# ERpcuk.net
KiCad netlist of a schematic drawn in EAGLE
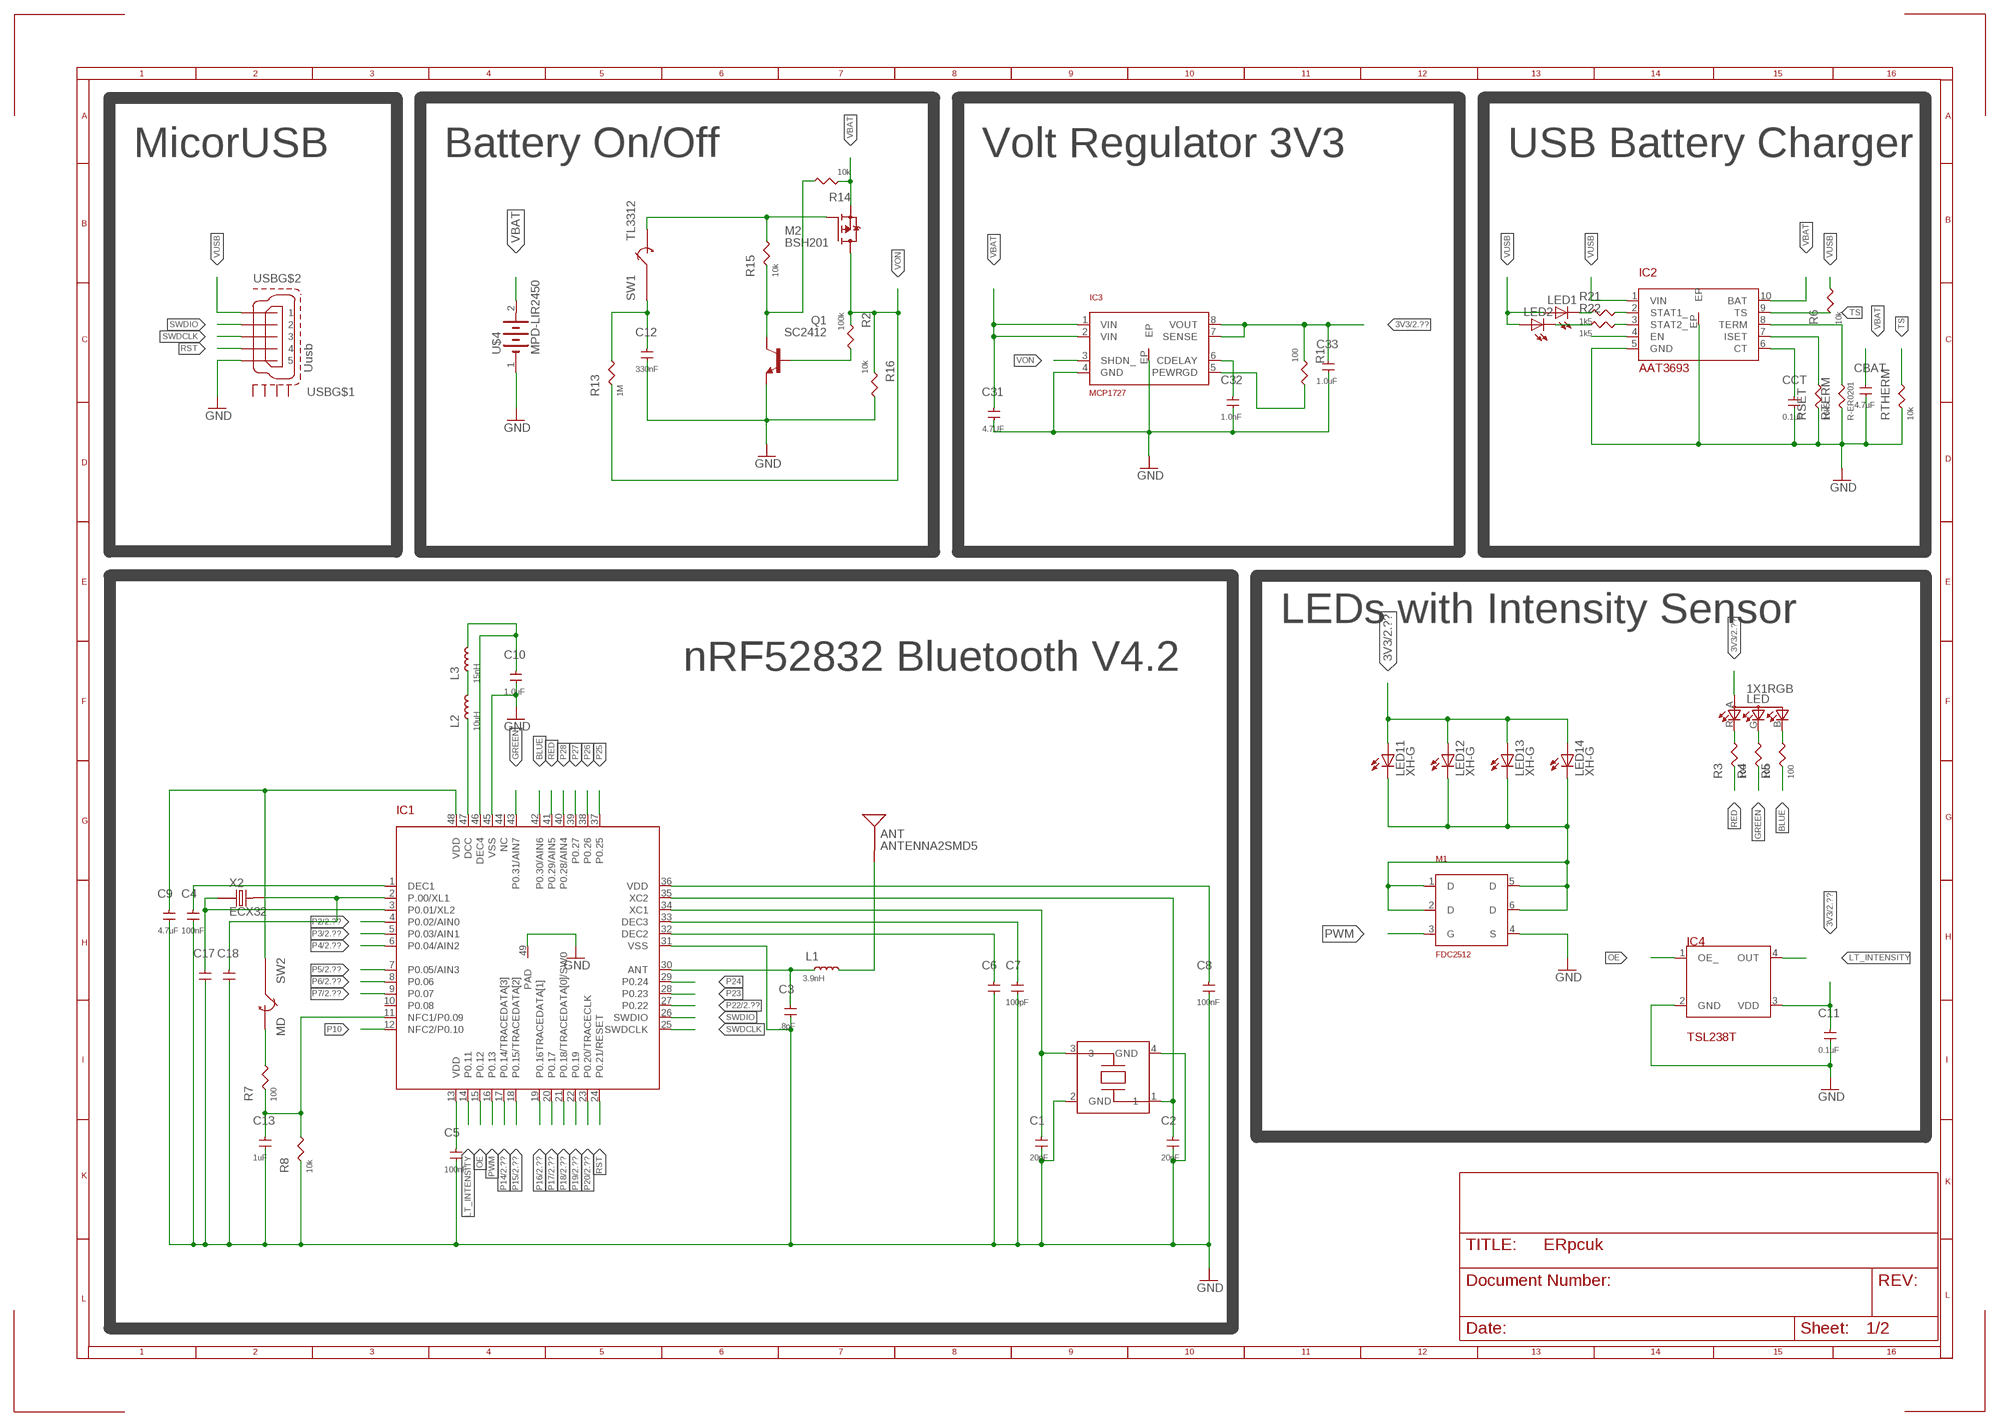
[diagram p0: schematic, sheet 1]
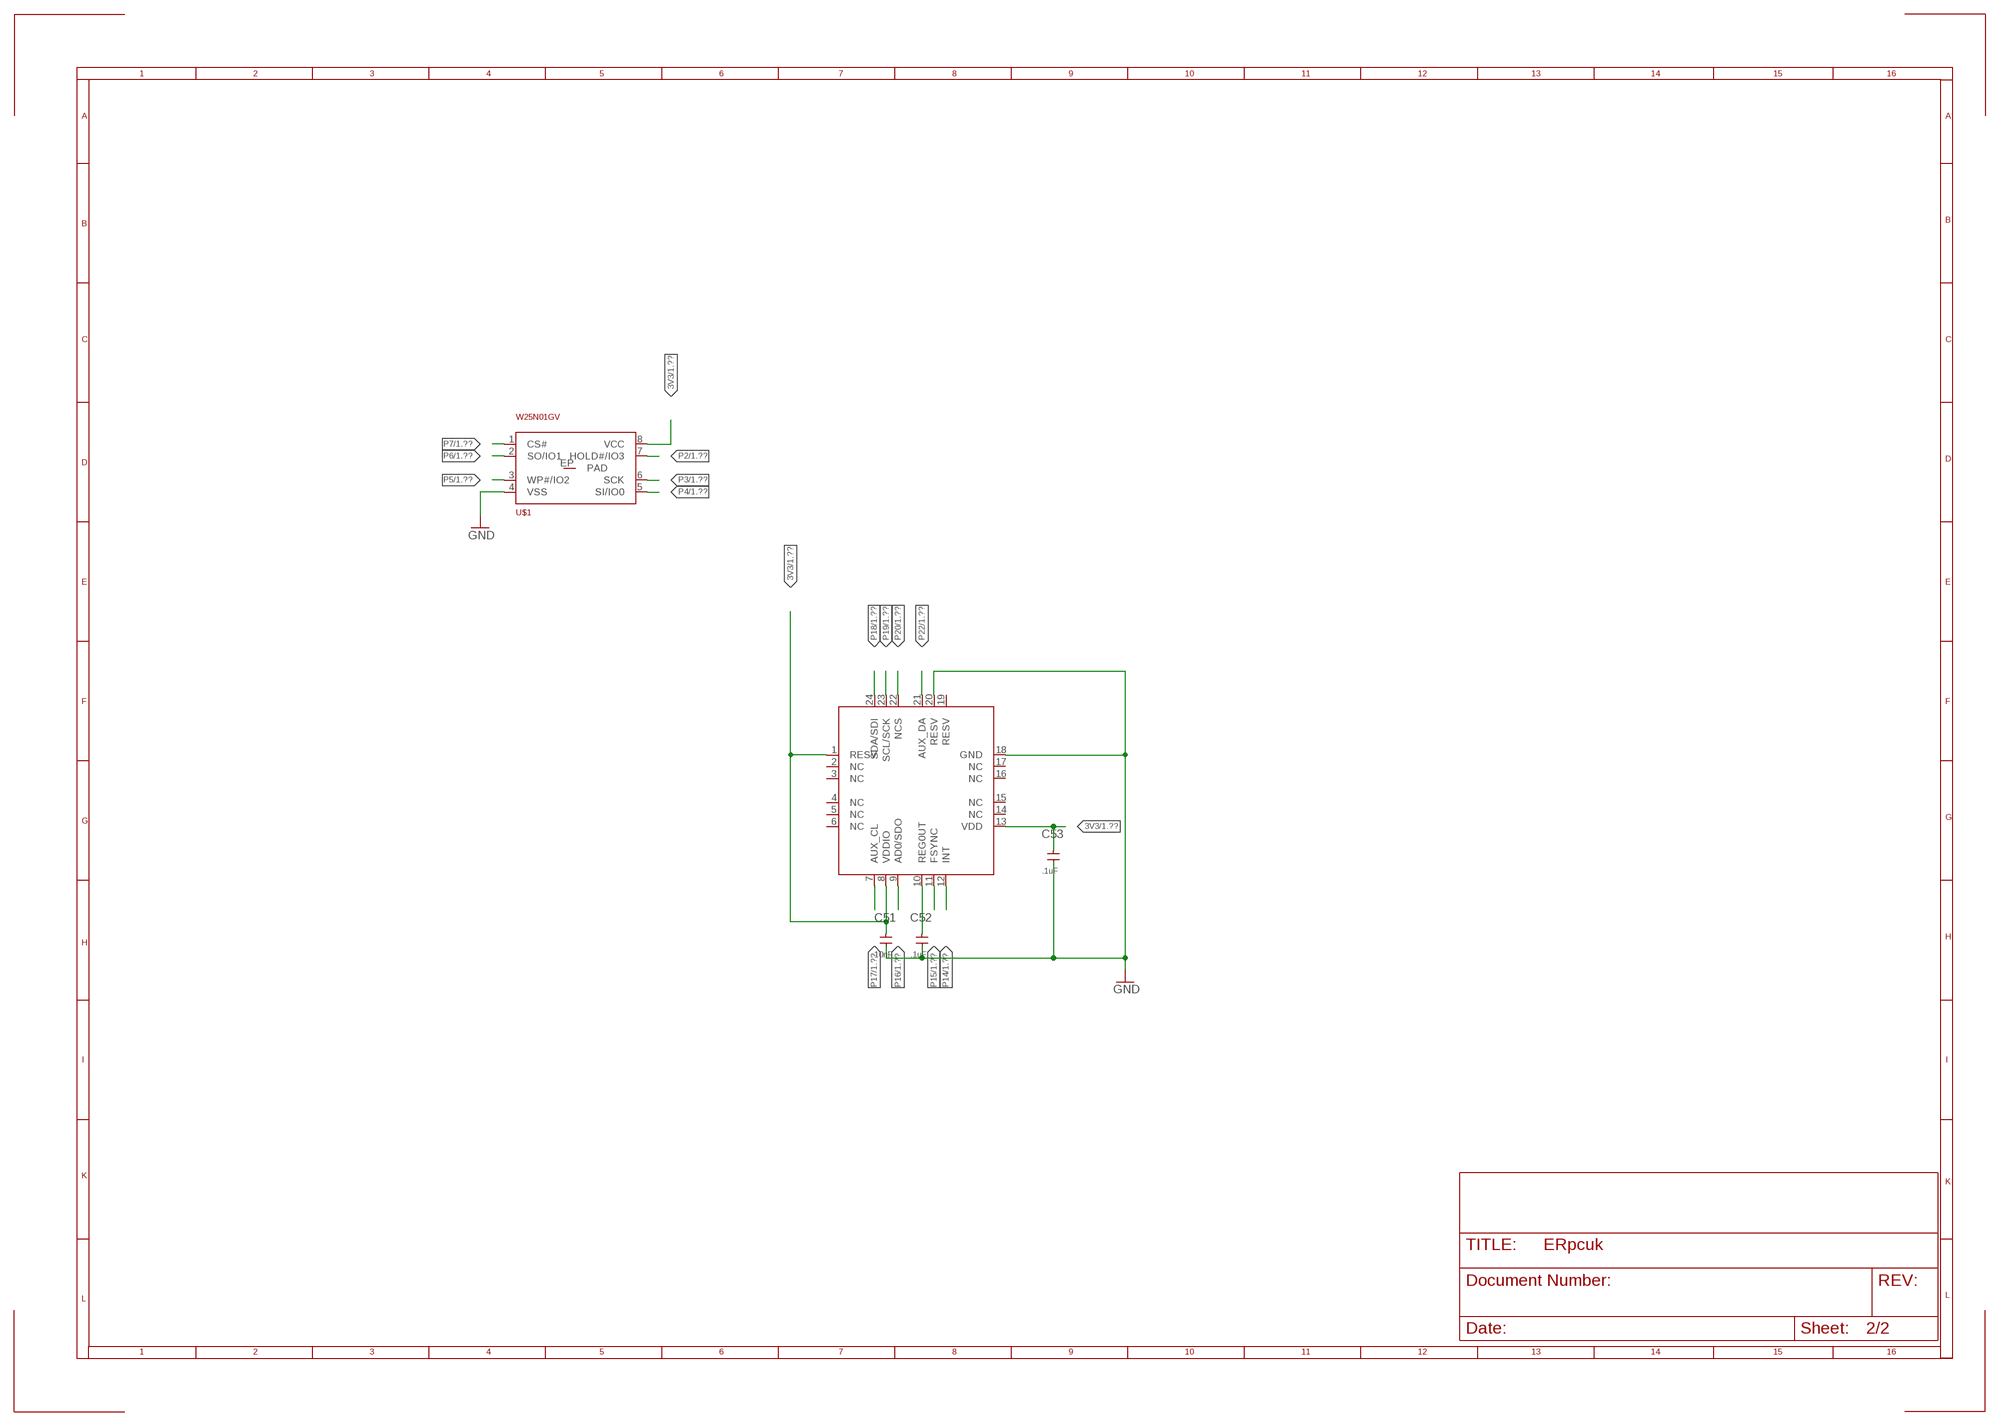
[diagram p1: schematic, sheet 2]

(export (version "E")
  (design (tool "Eeschema 10.0.6"))
  (components
    (comp (ref "C51")
      (value "10nF")
      (footprint "eagle-import:C0201")
      (libsource (lib "eagle-import") (part "C-ER201"))
    )
    (comp (ref "C52")
      (value ".1uF")
      (footprint "eagle-import:C0201")
      (libsource (lib "eagle-import") (part "C-ER201"))
    )
    (comp (ref "C53")
      (value ".1uF")
      (footprint "eagle-import:C0201")
      (libsource (lib "eagle-import") (part "C-ER201"))
    )
    (comp (ref "IC5")
      (value "MPU9250")
      (footprint "eagle-import:3X3_24_QFN_CORRECTED")
      (libsource (lib "eagle-import") (part "MPU9250_CORRECTED"))
    )
    (comp (ref "U$1")
      (value "W25N01GV")
      (footprint "eagle-import:8WSON6X8")
      (libsource (lib "eagle-import") (part "W25N01GV"))
    )
    (comp (ref "ANT")
      (value "ANTENNA2SMD5")
      (footprint "eagle-import:ANTENNA-CHIP5")
      (libsource (lib "eagle-import") (part "ANTENNA2SMD5"))
    )
    (comp (ref "C1")
      (value "20pF")
      (footprint "eagle-import:C0201")
      (libsource (lib "eagle-import") (part "C-ER201"))
    )
    (comp (ref "C2")
      (value "20pF")
      (footprint "eagle-import:C0201")
      (libsource (lib "eagle-import") (part "C-ER201"))
    )
    (comp (ref "C3")
      (value ".8pF")
      (footprint "eagle-import:C0201")
      (libsource (lib "eagle-import") (part "C-ER201"))
    )
    (comp (ref "C4")
      (value "100nF")
      (footprint "eagle-import:C0201")
      (libsource (lib "eagle-import") (part "C-ER201"))
    )
    (comp (ref "C5")
      (value "100nF")
      (footprint "eagle-import:C0201")
      (libsource (lib "eagle-import") (part "C-ER201"))
    )
    (comp (ref "C6")
      (value "C-ER201")
      (footprint "eagle-import:C0201")
      (libsource (lib "eagle-import") (part "C-ER201"))
    )
    (comp (ref "C7")
      (value "100pF")
      (footprint "eagle-import:C0201")
      (libsource (lib "eagle-import") (part "C-ER201"))
    )
    (comp (ref "C8")
      (value "100nF")
      (footprint "eagle-import:C0201")
      (libsource (lib "eagle-import") (part "C-ER201"))
    )
    (comp (ref "C9")
      (value "4.7uF")
      (footprint "eagle-import:C0402")
      (libsource (lib "eagle-import") (part "C-ERC0402"))
    )
    (comp (ref "C10")
      (value "1.0uF")
      (footprint "eagle-import:C0201")
      (libsource (lib "eagle-import") (part "C-ER201"))
    )
    (comp (ref "C11")
      (value "0.1uF")
      (footprint "eagle-import:C0201")
      (libsource (lib "eagle-import") (part "C-ER201"))
    )
    (comp (ref "C12")
      (value "330nF")
      (footprint "eagle-import:C0201")
      (libsource (lib "eagle-import") (part "C-ER201"))
    )
    (comp (ref "C13")
      (value "1uF")
      (footprint "eagle-import:C0201")
      (libsource (lib "eagle-import") (part "C-ER201"))
    )
    (comp (ref "C17")
      (value "C-ER201")
      (footprint "eagle-import:C0201")
      (libsource (lib "eagle-import") (part "C-ER201"))
    )
    (comp (ref "C18")
      (value "C-ER201")
      (footprint "eagle-import:C0201")
      (libsource (lib "eagle-import") (part "C-ER201"))
    )
    (comp (ref "C31")
      (value "4.7UF")
      (footprint "eagle-import:C0402")
      (libsource (lib "eagle-import") (part "C-ERC0402"))
    )
    (comp (ref "C32")
      (value "1.0nF")
      (footprint "eagle-import:C0201")
      (libsource (lib "eagle-import") (part "C-ER201"))
    )
    (comp (ref "C33")
      (value "1.0uF")
      (footprint "eagle-import:C0201")
      (libsource (lib "eagle-import") (part "C-ER201"))
    )
    (comp (ref "CBAT")
      (value "4.7uF")
      (footprint "eagle-import:C0402")
      (libsource (lib "eagle-import") (part "C-ERC0402"))
    )
    (comp (ref "CCT")
      (value "0.1uF")
      (footprint "eagle-import:C0201")
      (libsource (lib "eagle-import") (part "C-ER201"))
    )
    (comp (ref "IC1")
      (value "NRF52832")
      (footprint "eagle-import:QFN48")
      (libsource (lib "eagle-import") (part "NRF52832"))
    )
    (comp (ref "IC2")
      (value "AAT3693")
      (footprint "eagle-import:AAT3693")
      (libsource (lib "eagle-import") (part "AAT3693"))
    )
    (comp (ref "IC3")
      (value "MCP1727")
      (footprint "eagle-import:DFN8-3X3")
      (libsource (lib "eagle-import") (part "MCP1727"))
    )
    (comp (ref "IC4")
      (value "TSL238T")
      (footprint "eagle-import:T4")
      (libsource (lib "eagle-import") (part "TSL238T"))
    )
    (comp (ref "L1")
      (value "3.9nH")
      (footprint "eagle-import:C0201")
      (libsource (lib "eagle-import") (part "L-ER0201"))
    )
    (comp (ref "L2")
      (value "10uH")
      (footprint "eagle-import:R0603")
      (libsource (lib "eagle-import") (part "L-ERL603"))
    )
    (comp (ref "L3")
      (value "15nH")
      (footprint "eagle-import:C0201")
      (libsource (lib "eagle-import") (part "L-ER0201"))
    )
    (comp (ref "LED")
      (value "1X1RGB")
      (footprint "eagle-import:1X1")
      (libsource (lib "eagle-import") (part "1X1RGB"))
    )
    (comp (ref "LED1")
      (value "LEDCHIP-LED0603")
      (footprint "eagle-import:CHIP-LED0603")
      (libsource (lib "eagle-import") (part "LEDCHIP-LED0603"))
    )
    (comp (ref "LED2")
      (value "LEDCHIP-LED0603")
      (footprint "eagle-import:CHIP-LED0603")
      (libsource (lib "eagle-import") (part "LEDCHIP-LED0603"))
    )
    (comp (ref "LED11")
      (value "XH-G")
      (footprint "eagle-import:XH-G")
      (libsource (lib "eagle-import") (part "XH-G"))
    )
    (comp (ref "LED12")
      (value "XH-G")
      (footprint "eagle-import:XH-G")
      (libsource (lib "eagle-import") (part "XH-G"))
    )
    (comp (ref "LED13")
      (value "XH-G")
      (footprint "eagle-import:XH-G")
      (libsource (lib "eagle-import") (part "XH-G"))
    )
    (comp (ref "LED14")
      (value "XH-G")
      (footprint "eagle-import:XH-G")
      (libsource (lib "eagle-import") (part "XH-G"))
    )
    (comp (ref "M1")
      (value "FDC2512")
      (footprint "eagle-import:SSOT6")
      (libsource (lib "eagle-import") (part "FDC2512"))
    )
    (comp (ref "M2")
      (value "BSH201")
      (footprint "eagle-import:SOT23")
      (libsource (lib "eagle-import") (part "BSH201"))
    )
    (comp (ref "Q1")
      (value "SC2412")
      (footprint "eagle-import:SC59-BEC")
      (libsource (lib "eagle-import") (part "SC2412"))
    )
    (comp (ref "R1")
      (value "100")
      (footprint "eagle-import:R0201")
      (libsource (lib "eagle-import") (part "R-ER0201"))
    )
    (comp (ref "R2")
      (value "100k")
      (footprint "eagle-import:R0201")
      (libsource (lib "eagle-import") (part "R-ER0201"))
    )
    (comp (ref "R3")
      (value "100")
      (footprint "eagle-import:R0201")
      (libsource (lib "eagle-import") (part "R-ER0201"))
    )
    (comp (ref "R4")
      (value "100")
      (footprint "eagle-import:R0201")
      (libsource (lib "eagle-import") (part "R-ER0201"))
    )
    (comp (ref "R5")
      (value "100")
      (footprint "eagle-import:R0201")
      (libsource (lib "eagle-import") (part "R-ER0201"))
    )
    (comp (ref "R6")
      (value "10k")
      (footprint "eagle-import:R0201")
      (libsource (lib "eagle-import") (part "R-ER0201"))
    )
    (comp (ref "R7")
      (value "100")
      (footprint "eagle-import:R0201")
      (libsource (lib "eagle-import") (part "R-ER0201"))
    )
    (comp (ref "R8")
      (value "10k")
      (footprint "eagle-import:R0201")
      (libsource (lib "eagle-import") (part "R-ER0201"))
    )
    (comp (ref "R13")
      (value "1M")
      (footprint "eagle-import:R0201")
      (libsource (lib "eagle-import") (part "R-ER0201"))
    )
    (comp (ref "R14")
      (value "10k")
      (footprint "eagle-import:R0201")
      (libsource (lib "eagle-import") (part "R-ER0201"))
    )
    (comp (ref "R15")
      (value "10k")
      (footprint "eagle-import:R0201")
      (libsource (lib "eagle-import") (part "R-ER0201"))
    )
    (comp (ref "R16")
      (value "10k")
      (footprint "eagle-import:R0201")
      (libsource (lib "eagle-import") (part "R-ER0201"))
    )
    (comp (ref "R21")
      (value "1k5")
      (footprint "eagle-import:R0201")
      (libsource (lib "eagle-import") (part "R-ER0201"))
    )
    (comp (ref "R22")
      (value "1k5")
      (footprint "eagle-import:R0201")
      (libsource (lib "eagle-import") (part "R-ER0201"))
    )
    (comp (ref "RSET")
      (value "16k5")
      (footprint "eagle-import:R0201")
      (libsource (lib "eagle-import") (part "R-ER0201"))
    )
    (comp (ref "RTERM")
      (value "R-ER0201")
      (footprint "eagle-import:R0201")
      (libsource (lib "eagle-import") (part "R-ER0201"))
    )
    (comp (ref "RTHERM")
      (value "10k")
      (footprint "eagle-import:R0201")
      (libsource (lib "eagle-import") (part "R-ER0201"))
    )
    (comp (ref "SW1")
      (value "TL3312")
      (footprint "eagle-import:TL3312")
      (libsource (lib "eagle-import") (part "TL3312"))
    )
    (comp (ref "SW2") (value "MD") (footprint "eagle-import:MD") (libsource (lib "eagle-import") (part "MD")))
    (comp (ref "U$4")
      (value "MPD-LIR2450")
      (footprint "eagle-import:LIR2450")
      (libsource (lib "eagle-import") (part "MPD-LIR2450"))
    )
    (comp (ref "USB")
      (value "Uusb")
      (footprint "eagle-import:ZX62R-B-5P")
      (libsource (lib "eagle-import") (part "MICRO-USB-SHIELD-ZX62R-B-5P"))
    )
    (comp (ref "X1")
      (value "FA-128")
      (footprint "eagle-import:FA-128")
      (libsource (lib "eagle-import") (part "FA-128"))
    )
    (comp (ref "X2")
      (value "ECX32")
      (footprint "eagle-import:ECX39")
      (libsource (lib "eagle-import") (part "ECX32"))
    )
  )
  (nets
    (net (code "1") (name "3V3") (class "Default")
      (node (ref "C11") (pin "2") (pinfunction "P$2_2") (pintype "bidirectional"))
      (node (ref "C33") (pin "2") (pinfunction "P$2_2") (pintype "bidirectional"))
      (node (ref "C5") (pin "2") (pinfunction "P$2_2") (pintype "bidirectional"))
      (node (ref "C51") (pin "2") (pinfunction "P$2_2") (pintype "bidirectional"))
      (node (ref "C53") (pin "2") (pinfunction "P$2_2") (pintype "bidirectional"))
      (node (ref "C8") (pin "2") (pinfunction "P$2_2") (pintype "bidirectional"))
      (node (ref "C9") (pin "2") (pinfunction "P$2_2") (pintype "bidirectional"))
      (node (ref "IC1") (pin "13") (pinfunction "VDD_13") (pintype "bidirectional"))
      (node (ref "IC1") (pin "36") (pinfunction "VDD_36") (pintype "bidirectional"))
      (node (ref "IC1") (pin "48") (pinfunction "VDD_48") (pintype "bidirectional"))
      (node (ref "IC3") (pin "7") (pinfunction "SENSE_7") (pintype "bidirectional"))
      (node (ref "IC3") (pin "8") (pinfunction "VOUT_8") (pintype "bidirectional"))
      (node (ref "IC4") (pin "3") (pinfunction "VDD_3") (pintype "bidirectional"))
      (node (ref "IC5") (pin "1") (pinfunction "RESV_1") (pintype "bidirectional"))
      (node (ref "IC5") (pin "13") (pinfunction "VDD_13") (pintype "bidirectional"))
      (node (ref "IC5") (pin "8") (pinfunction "VDDIO_8") (pintype "bidirectional"))
      (node (ref "LED") (pin "A") (pinfunction "A2_A") (pintype "passive"))
      (node (ref "LED11") (pin "2") (pinfunction "A_2") (pintype "passive"))
      (node (ref "LED12") (pin "2") (pinfunction "A_2") (pintype "passive"))
      (node (ref "LED13") (pin "2") (pinfunction "A_2") (pintype "passive"))
      (node (ref "LED14") (pin "2") (pinfunction "A_2") (pintype "passive"))
      (node (ref "R1") (pin "1") (pinfunction "P$1_1") (pintype "bidirectional"))
      (node (ref "SW2") (pin "P$1") (pinfunction "1_P$1") (pintype "bidirectional"))
      (node (ref "U$1") (pin "8") (pinfunction "VCC_8") (pintype "bidirectional"))
    )
    (net (code "2") (name "BLUE") (class "Default")
      (node (ref "IC1") (pin "42") (pinfunction "P0.30/AIN6_42") (pintype "bidirectional"))
      (node (ref "R5") (pin "1") (pinfunction "P$1_1") (pintype "bidirectional"))
    )
    (net (code "3") (name "GND") (class "Default")
      (node (ref "C1") (pin "1") (pinfunction "P$1_1") (pintype "bidirectional"))
      (node (ref "C10") (pin "1") (pinfunction "P$1_1") (pintype "bidirectional"))
      (node (ref "C11") (pin "1") (pinfunction "P$1_1") (pintype "bidirectional"))
      (node (ref "C12") (pin "1") (pinfunction "P$1_1") (pintype "bidirectional"))
      (node (ref "C13") (pin "1") (pinfunction "P$1_1") (pintype "bidirectional"))
      (node (ref "C17") (pin "1") (pinfunction "P$1_1") (pintype "bidirectional"))
      (node (ref "C18") (pin "1") (pinfunction "P$1_1") (pintype "bidirectional"))
      (node (ref "C2") (pin "1") (pinfunction "P$1_1") (pintype "bidirectional"))
      (node (ref "C3") (pin "1") (pinfunction "P$1_1") (pintype "bidirectional"))
      (node (ref "C31") (pin "1") (pinfunction "P$1_1") (pintype "bidirectional"))
      (node (ref "C32") (pin "1") (pinfunction "P$1_1") (pintype "bidirectional"))
      (node (ref "C33") (pin "1") (pinfunction "P$1_1") (pintype "bidirectional"))
      (node (ref "C4") (pin "1") (pinfunction "P$1_1") (pintype "bidirectional"))
      (node (ref "C5") (pin "1") (pinfunction "P$1_1") (pintype "bidirectional"))
      (node (ref "C51") (pin "1") (pinfunction "P$1_1") (pintype "bidirectional"))
      (node (ref "C52") (pin "1") (pinfunction "P$1_1") (pintype "bidirectional"))
      (node (ref "C53") (pin "1") (pinfunction "P$1_1") (pintype "bidirectional"))
      (node (ref "C6") (pin "1") (pinfunction "P$1_1") (pintype "bidirectional"))
      (node (ref "C7") (pin "1") (pinfunction "P$1_1") (pintype "bidirectional"))
      (node (ref "C8") (pin "1") (pinfunction "P$1_1") (pintype "bidirectional"))
      (node (ref "C9") (pin "1") (pinfunction "P$1_1") (pintype "bidirectional"))
      (node (ref "CBAT") (pin "1") (pinfunction "P$1_1") (pintype "bidirectional"))
      (node (ref "CCT") (pin "1") (pinfunction "P$1_1") (pintype "bidirectional"))
      (node (ref "IC1") (pin "31") (pinfunction "VSS_31") (pintype "bidirectional"))
      (node (ref "IC1") (pin "45") (pinfunction "VSS_45") (pintype "bidirectional"))
      (node (ref "IC1") (pin "49") (pinfunction "PAD_49") (pintype "bidirectional"))
      (node (ref "IC2") (pin "5") (pinfunction "GND_5") (pintype "bidirectional"))
      (node (ref "IC2") (pin "EP") (pinfunction "EP_EP") (pintype "bidirectional"))
      (node (ref "IC3") (pin "4") (pinfunction "GND_4") (pintype "bidirectional"))
      (node (ref "IC3") (pin "EP") (pinfunction "EP_EP") (pintype "bidirectional"))
      (node (ref "IC4") (pin "2") (pinfunction "GND_2") (pintype "bidirectional"))
      (node (ref "IC5") (pin "18") (pinfunction "GND_18") (pintype "bidirectional"))
      (node (ref "IC5") (pin "20") (pinfunction "RESV_20") (pintype "bidirectional"))
      (node (ref "M1") (pin "4") (pinfunction "S_4") (pintype "bidirectional"))
      (node (ref "Q1") (pin "E") (pinfunction "E_E") (pintype "passive"))
      (node (ref "R16") (pin "2") (pinfunction "P$2_2") (pintype "bidirectional"))
      (node (ref "R8") (pin "1") (pinfunction "P$1_1") (pintype "bidirectional"))
      (node (ref "RSET") (pin "1") (pinfunction "P$1_1") (pintype "bidirectional"))
      (node (ref "RTERM") (pin "1") (pinfunction "P$1_1") (pintype "bidirectional"))
      (node (ref "RTHERM") (pin "1") (pinfunction "P$1_1") (pintype "bidirectional"))
      (node (ref "U$1") (pin "4") (pinfunction "VSS_4") (pintype "bidirectional"))
      (node (ref "U$4") (pin "1") (pinfunction "-_1") (pintype "passive"))
      (node (ref "USB") (pin "1") (pinfunction "5_1") (pintype "input"))
      (node (ref "X1") (pin "2") (pinfunction "GND_2") (pintype "bidirectional"))
      (node (ref "X1") (pin "4") (pinfunction "GND_4") (pintype "bidirectional"))
    )
    (net (code "4") (name "GREEN") (class "Default")
      (node (ref "IC1") (pin "43") (pinfunction "P0.31/AIN7_43") (pintype "bidirectional"))
      (node (ref "R4") (pin "1") (pinfunction "P$1_1") (pintype "bidirectional"))
    )
    (net (code "5") (name "LT_INTENSITY") (class "Default")
      (node (ref "IC1") (pin "14") (pinfunction "P0.11_14") (pintype "bidirectional"))
      (node (ref "IC4") (pin "4") (pinfunction "OUT_4") (pintype "bidirectional"))
    )
    (net (code "6") (name "Net-(ANT-SIGNAL)") (class "Default")
      (node (ref "ANT") (pin "FEED") (pinfunction "SIGNAL_FEED") (pintype "bidirectional"))
      (node (ref "L1") (pin "2") (pinfunction "P$2_2") (pintype "bidirectional"))
    )
    (net (code "7") (name "Net-(C1-P$2)") (class "Default")
      (node (ref "C1") (pin "2") (pinfunction "P$2_2") (pintype "bidirectional"))
      (node (ref "IC1") (pin "34") (pinfunction "XC1_34") (pintype "bidirectional"))
      (node (ref "X1") (pin "3") (pinfunction "3_3") (pintype "bidirectional"))
    )
    (net (code "8") (name "Net-(C2-P$2)") (class "Default")
      (node (ref "C2") (pin "2") (pinfunction "P$2_2") (pintype "bidirectional"))
      (node (ref "IC1") (pin "35") (pinfunction "XC2_35") (pintype "bidirectional"))
      (node (ref "X1") (pin "1") (pinfunction "1_1") (pintype "bidirectional"))
    )
    (net (code "9") (name "Net-(C3-P$2)") (class "Default")
      (node (ref "C3") (pin "2") (pinfunction "P$2_2") (pintype "bidirectional"))
      (node (ref "IC1") (pin "30") (pinfunction "ANT_30") (pintype "bidirectional"))
      (node (ref "L1") (pin "1") (pinfunction "P$1_1") (pintype "bidirectional"))
    )
    (net (code "10") (name "Net-(C4-P$2)") (class "Default")
      (node (ref "C4") (pin "2") (pinfunction "P$2_2") (pintype "bidirectional"))
      (node (ref "IC1") (pin "1") (pinfunction "DEC1_1") (pintype "bidirectional"))
    )
    (net (code "11") (name "Net-(C6-P$2)") (class "Default")
      (node (ref "C6") (pin "2") (pinfunction "P$2_2") (pintype "bidirectional"))
      (node (ref "IC1") (pin "32") (pinfunction "DEC2_32") (pintype "bidirectional"))
    )
    (net (code "12") (name "Net-(C7-P$2)") (class "Default")
      (node (ref "C7") (pin "2") (pinfunction "P$2_2") (pintype "bidirectional"))
      (node (ref "IC1") (pin "33") (pinfunction "DEC3_33") (pintype "bidirectional"))
    )
    (net (code "13") (name "Net-(C10-P$2)") (class "Default")
      (node (ref "C10") (pin "2") (pinfunction "P$2_2") (pintype "bidirectional"))
      (node (ref "IC1") (pin "46") (pinfunction "DEC4_46") (pintype "bidirectional"))
      (node (ref "L3") (pin "2") (pinfunction "P$2_2") (pintype "bidirectional"))
    )
    (net (code "14") (name "Net-(C12-P$2)") (class "Default")
      (node (ref "C12") (pin "2") (pinfunction "P$2_2") (pintype "bidirectional"))
      (node (ref "R13") (pin "2") (pinfunction "P$2_2") (pintype "bidirectional"))
      (node (ref "SW1") (pin "1") (pinfunction "1_1") (pintype "bidirectional"))
    )
    (net (code "15") (name "Net-(C13-P$2)") (class "Default")
      (node (ref "C13") (pin "2") (pinfunction "P$2_2") (pintype "bidirectional"))
      (node (ref "IC1") (pin "11") (pinfunction "NFC1/P0.09_11") (pintype "bidirectional"))
      (node (ref "R7") (pin "1") (pinfunction "P$1_1") (pintype "bidirectional"))
      (node (ref "R8") (pin "2") (pinfunction "P$2_2") (pintype "bidirectional"))
    )
    (net (code "16") (name "Net-(C17-P$2)") (class "Default")
      (node (ref "C17") (pin "2") (pinfunction "P$2_2") (pintype "bidirectional"))
      (node (ref "IC1") (pin "3") (pinfunction "P0.01/XL2_3") (pintype "bidirectional"))
      (node (ref "X2") (pin "P$1") (pinfunction "1_P$1") (pintype "passive"))
    )
    (net (code "17") (name "Net-(C18-P$2)") (class "Default")
      (node (ref "C18") (pin "2") (pinfunction "P$2_2") (pintype "bidirectional"))
      (node (ref "IC1") (pin "2") (pinfunction "P.00/XL1_2") (pintype "bidirectional"))
      (node (ref "X2") (pin "P$2") (pinfunction "2_P$2") (pintype "passive"))
    )
    (net (code "18") (name "Net-(C32-P$2)") (class "Default")
      (node (ref "C32") (pin "2") (pinfunction "P$2_2") (pintype "bidirectional"))
      (node (ref "IC3") (pin "6") (pinfunction "CDELAY_6") (pintype "bidirectional"))
    )
    (net (code "19") (name "Net-(C52-P$2)") (class "Default")
      (node (ref "C52") (pin "2") (pinfunction "P$2_2") (pintype "bidirectional"))
      (node (ref "IC5") (pin "10") (pinfunction "REG0UT_10") (pintype "bidirectional"))
    )
    (net (code "20") (name "Net-(CCT-P$2)") (class "Default")
      (node (ref "CCT") (pin "2") (pinfunction "P$2_2") (pintype "bidirectional"))
      (node (ref "IC2") (pin "6") (pinfunction "CT_6") (pintype "bidirectional"))
    )
    (net (code "21") (name "Net-(IC1-DCC)") (class "Default")
      (node (ref "IC1") (pin "47") (pinfunction "DCC_47") (pintype "bidirectional"))
      (node (ref "L2") (pin "1") (pinfunction "P$1_1") (pintype "bidirectional"))
    )
    (net (code "22") (name "Net-(IC2-ISET)") (class "Default")
      (node (ref "IC2") (pin "7") (pinfunction "ISET_7") (pintype "bidirectional"))
      (node (ref "RSET") (pin "2") (pinfunction "P$2_2") (pintype "bidirectional"))
    )
    (net (code "23") (name "Net-(IC2-STAT1_)") (class "Default")
      (node (ref "IC2") (pin "2") (pinfunction "STAT1__2") (pintype "bidirectional"))
      (node (ref "R21") (pin "2") (pinfunction "P$2_2") (pintype "bidirectional"))
    )
    (net (code "24") (name "Net-(IC2-STAT2_)") (class "Default")
      (node (ref "IC2") (pin "3") (pinfunction "STAT2__3") (pintype "bidirectional"))
      (node (ref "R22") (pin "2") (pinfunction "P$2_2") (pintype "bidirectional"))
    )
    (net (code "25") (name "Net-(IC2-TERM)") (class "Default")
      (node (ref "IC2") (pin "8") (pinfunction "TERM_8") (pintype "bidirectional"))
      (node (ref "RTERM") (pin "2") (pinfunction "P$2_2") (pintype "bidirectional"))
    )
    (net (code "26") (name "Net-(IC3-PEWRGD)") (class "Default")
      (node (ref "IC3") (pin "5") (pinfunction "PEWRGD_5") (pintype "bidirectional"))
      (node (ref "R1") (pin "2") (pinfunction "P$2_2") (pintype "bidirectional"))
    )
    (net (code "27") (name "Net-(L2-P$2)") (class "Default")
      (node (ref "L2") (pin "2") (pinfunction "P$2_2") (pintype "bidirectional"))
      (node (ref "L3") (pin "1") (pinfunction "P$1_1") (pintype "bidirectional"))
    )
    (net (code "28") (name "Net-(LED-CBLUE)") (class "Default")
      (node (ref "LED") (pin "G") (pinfunction "CBLUE_G") (pintype "passive"))
      (node (ref "R4") (pin "2") (pinfunction "P$2_2") (pintype "bidirectional"))
    )
    (net (code "29") (name "Net-(LED-CGREEN)") (class "Default")
      (node (ref "LED") (pin "B") (pinfunction "CGREEN_B") (pintype "passive"))
      (node (ref "R5") (pin "2") (pinfunction "P$2_2") (pintype "bidirectional"))
    )
    (net (code "30") (name "Net-(LED-CRED)") (class "Default")
      (node (ref "LED") (pin "R") (pinfunction "CRED_R") (pintype "passive"))
      (node (ref "R3") (pin "2") (pinfunction "P$2_2") (pintype "bidirectional"))
    )
    (net (code "31") (name "Net-(LED11-C)") (class "Default")
      (node (ref "LED11") (pin "1") (pinfunction "C_1") (pintype "passive"))
      (node (ref "LED12") (pin "1") (pinfunction "C_1") (pintype "passive"))
      (node (ref "LED13") (pin "1") (pinfunction "C_1") (pintype "passive"))
      (node (ref "LED14") (pin "1") (pinfunction "C_1") (pintype "passive"))
      (node (ref "M1") (pin "1") (pinfunction "D_1") (pintype "bidirectional"))
      (node (ref "M1") (pin "2") (pinfunction "D_2") (pintype "bidirectional"))
      (node (ref "M1") (pin "5") (pinfunction "D_5") (pintype "bidirectional"))
      (node (ref "M1") (pin "6") (pinfunction "D_6") (pintype "bidirectional"))
    )
    (net (code "32") (name "Net-(M2-G)") (class "Default")
      (node (ref "M2") (pin "1") (pinfunction "G_1") (pintype "passive"))
      (node (ref "R15") (pin "2") (pinfunction "P$2_2") (pintype "bidirectional"))
      (node (ref "SW1") (pin "3") (pinfunction "2_3") (pintype "bidirectional"))
    )
    (net (code "33") (name "Net-(R2-P$2)") (class "Default")
      (node (ref "Q1") (pin "B") (pinfunction "B_B") (pintype "passive"))
      (node (ref "R2") (pin "2") (pinfunction "P$2_2") (pintype "bidirectional"))
    )
    (net (code "34") (name "Net-(R7-P$2)") (class "Default")
      (node (ref "R7") (pin "2") (pinfunction "P$2_2") (pintype "bidirectional"))
      (node (ref "SW2") (pin "P$2") (pinfunction "2_P$2") (pintype "bidirectional"))
    )
    (net (code "35") (name "Net-(R14-P$2)") (class "Default")
      (node (ref "Q1") (pin "C") (pinfunction "C_C") (pintype "passive"))
      (node (ref "R14") (pin "2") (pinfunction "P$2_2") (pintype "bidirectional"))
      (node (ref "R15") (pin "1") (pinfunction "P$1_1") (pintype "bidirectional"))
    )
    (net (code "36") (name "Net-(R21-P$1)") (class "Default")
      (node (ref "LED1") (pin "C") (pinfunction "C_C") (pintype "passive"))
      (node (ref "R21") (pin "1") (pinfunction "P$1_1") (pintype "bidirectional"))
    )
    (net (code "37") (name "Net-(R22-P$1)") (class "Default")
      (node (ref "LED2") (pin "C") (pinfunction "C_C") (pintype "passive"))
      (node (ref "R22") (pin "1") (pinfunction "P$1_1") (pintype "bidirectional"))
    )
    (net (code "38") (name "OE") (class "Default")
      (node (ref "IC1") (pin "15") (pinfunction "P0.12_15") (pintype "bidirectional"))
      (node (ref "IC4") (pin "1") (pinfunction "OE__1") (pintype "bidirectional"))
    )
    (net (code "39") (name "P2") (class "Default")
      (node (ref "IC1") (pin "4") (pinfunction "P0.02/AIN0_4") (pintype "bidirectional"))
      (node (ref "U$1") (pin "7") (pinfunction "HOLD#/IO3_7") (pintype "bidirectional"))
    )
    (net (code "40") (name "P3") (class "Default")
      (node (ref "IC1") (pin "5") (pinfunction "P0.03/AIN1_5") (pintype "bidirectional"))
      (node (ref "U$1") (pin "6") (pinfunction "SCK_6") (pintype "bidirectional"))
    )
    (net (code "41") (name "P4") (class "Default")
      (node (ref "IC1") (pin "6") (pinfunction "P0.04/AIN2_6") (pintype "bidirectional"))
      (node (ref "U$1") (pin "5") (pinfunction "SI/IO0_5") (pintype "bidirectional"))
    )
    (net (code "42") (name "P5") (class "Default")
      (node (ref "IC1") (pin "7") (pinfunction "P0.05/AIN3_7") (pintype "bidirectional"))
      (node (ref "U$1") (pin "3") (pinfunction "WP#/IO2_3") (pintype "bidirectional"))
    )
    (net (code "43") (name "P6") (class "Default")
      (node (ref "IC1") (pin "8") (pinfunction "P0.06_8") (pintype "bidirectional"))
      (node (ref "U$1") (pin "2") (pinfunction "SO/IO1_2") (pintype "bidirectional"))
    )
    (net (code "44") (name "P7") (class "Default")
      (node (ref "IC1") (pin "9") (pinfunction "P0.07_9") (pintype "bidirectional"))
      (node (ref "U$1") (pin "1") (pinfunction "CS#_1") (pintype "bidirectional"))
    )
    (net (code "45") (name "P10") (class "Default")
      (node (ref "IC1") (pin "12") (pinfunction "NFC2/P0.10_12") (pintype "bidirectional"))
    )
    (net (code "46") (name "P14") (class "Default")
      (node (ref "IC1") (pin "17") (pinfunction "P0.14/TRACEDATA[3]_17") (pintype "bidirectional"))
      (node (ref "IC5") (pin "12") (pinfunction "INT_12") (pintype "bidirectional"))
    )
    (net (code "47") (name "P15") (class "Default")
      (node (ref "IC1") (pin "18") (pinfunction "P0.15/TRACEDATA[2]_18") (pintype "bidirectional"))
      (node (ref "IC5") (pin "11") (pinfunction "FSYNC_11") (pintype "bidirectional"))
    )
    (net (code "48") (name "P16") (class "Default")
      (node (ref "IC1") (pin "19") (pinfunction "P0.16TRACEDATA[1]_19") (pintype "bidirectional"))
      (node (ref "IC5") (pin "9") (pinfunction "AD0/SDO_9") (pintype "bidirectional"))
    )
    (net (code "49") (name "P17") (class "Default")
      (node (ref "IC1") (pin "20") (pinfunction "P0.17_20") (pintype "bidirectional"))
      (node (ref "IC5") (pin "7") (pinfunction "AUX_CL_7") (pintype "bidirectional"))
    )
    (net (code "50") (name "P18") (class "Default")
      (node (ref "IC1") (pin "21") (pinfunction "P0.18/TRACEDATA[0]/SW0_21") (pintype "bidirectional"))
      (node (ref "IC5") (pin "24") (pinfunction "SDA/SDI_24") (pintype "bidirectional"))
    )
    (net (code "51") (name "P19") (class "Default")
      (node (ref "IC1") (pin "22") (pinfunction "P0.19_22") (pintype "bidirectional"))
      (node (ref "IC5") (pin "23") (pinfunction "SCL/SCK_23") (pintype "bidirectional"))
    )
    (net (code "52") (name "P20") (class "Default")
      (node (ref "IC1") (pin "23") (pinfunction "P0.20/TRACECLK_23") (pintype "bidirectional"))
      (node (ref "IC5") (pin "22") (pinfunction "NCS_22") (pintype "bidirectional"))
    )
    (net (code "53") (name "P22") (class "Default")
      (node (ref "IC1") (pin "27") (pinfunction "P0.22_27") (pintype "bidirectional"))
      (node (ref "IC5") (pin "21") (pinfunction "AUX_DA_21") (pintype "bidirectional"))
    )
    (net (code "54") (name "P23") (class "Default")
      (node (ref "IC1") (pin "28") (pinfunction "P0.23_28") (pintype "bidirectional"))
    )
    (net (code "55") (name "P24") (class "Default")
      (node (ref "IC1") (pin "29") (pinfunction "P0.24_29") (pintype "bidirectional"))
    )
    (net (code "56") (name "P25") (class "Default")
      (node (ref "IC1") (pin "37") (pinfunction "P0.25_37") (pintype "bidirectional"))
    )
    (net (code "57") (name "P26") (class "Default")
      (node (ref "IC1") (pin "38") (pinfunction "P0.26_38") (pintype "bidirectional"))
    )
    (net (code "58") (name "P27") (class "Default")
      (node (ref "IC1") (pin "39") (pinfunction "P0.27_39") (pintype "bidirectional"))
    )
    (net (code "59") (name "P28") (class "Default")
      (node (ref "IC1") (pin "40") (pinfunction "P0.28/AIN4_40") (pintype "bidirectional"))
    )
    (net (code "60") (name "PWM") (class "Default")
      (node (ref "IC1") (pin "16") (pinfunction "P0.13_16") (pintype "bidirectional"))
      (node (ref "M1") (pin "3") (pinfunction "G_3") (pintype "bidirectional"))
    )
    (net (code "61") (name "RED") (class "Default")
      (node (ref "IC1") (pin "41") (pinfunction "P0.29/AIN5_41") (pintype "bidirectional"))
      (node (ref "R3") (pin "1") (pinfunction "P$1_1") (pintype "bidirectional"))
    )
    (net (code "62") (name "RST") (class "Default")
      (node (ref "IC1") (pin "24") (pinfunction "P0.21/RESET_24") (pintype "bidirectional"))
      (node (ref "USB") (pin "2") (pinfunction "4_2") (pintype "input"))
    )
    (net (code "63") (name "SWDCLK") (class "Default")
      (node (ref "IC1") (pin "25") (pinfunction "SWDCLK_25") (pintype "bidirectional"))
      (node (ref "USB") (pin "3") (pinfunction "3_3") (pintype "input"))
    )
    (net (code "64") (name "SWDIO") (class "Default")
      (node (ref "IC1") (pin "26") (pinfunction "SWDIO_26") (pintype "bidirectional"))
      (node (ref "USB") (pin "4") (pinfunction "2_4") (pintype "input"))
    )
    (net (code "65") (name "TS") (class "Default")
      (node (ref "IC2") (pin "9") (pinfunction "TS_9") (pintype "bidirectional"))
      (node (ref "R6") (pin "1") (pinfunction "P$1_1") (pintype "bidirectional"))
      (node (ref "RTHERM") (pin "2") (pinfunction "P$2_2") (pintype "bidirectional"))
    )
    (net (code "66") (name "VBAT") (class "Default")
      (node (ref "C31") (pin "2") (pinfunction "P$2_2") (pintype "bidirectional"))
      (node (ref "CBAT") (pin "2") (pinfunction "P$2_2") (pintype "bidirectional"))
      (node (ref "IC2") (pin "10") (pinfunction "BAT_10") (pintype "bidirectional"))
      (node (ref "IC3") (pin "1") (pinfunction "VIN_1") (pintype "bidirectional"))
      (node (ref "IC3") (pin "2") (pinfunction "VIN_2") (pintype "bidirectional"))
      (node (ref "M2") (pin "2") (pinfunction "S_2") (pintype "passive"))
      (node (ref "R14") (pin "1") (pinfunction "P$1_1") (pintype "bidirectional"))
      (node (ref "U$4") (pin "2") (pinfunction "+_2") (pintype "passive"))
    )
    (net (code "67") (name "VON") (class "Default")
      (node (ref "IC3") (pin "3") (pinfunction "SHDN__3") (pintype "bidirectional"))
      (node (ref "M2") (pin "3") (pinfunction "D_3") (pintype "passive"))
      (node (ref "R13") (pin "1") (pinfunction "P$1_1") (pintype "bidirectional"))
      (node (ref "R16") (pin "1") (pinfunction "P$1_1") (pintype "bidirectional"))
      (node (ref "R2") (pin "1") (pinfunction "P$1_1") (pintype "bidirectional"))
    )
    (net (code "68") (name "VUSB") (class "Default")
      (node (ref "IC2") (pin "1") (pinfunction "VIN_1") (pintype "bidirectional"))
      (node (ref "IC2") (pin "4") (pinfunction "EN_4") (pintype "bidirectional"))
      (node (ref "LED1") (pin "A") (pinfunction "A_A") (pintype "passive"))
      (node (ref "LED2") (pin "A") (pinfunction "A_A") (pintype "passive"))
      (node (ref "R6") (pin "2") (pinfunction "P$2_2") (pintype "bidirectional"))
      (node (ref "USB") (pin "5") (pinfunction "1_5") (pintype "input"))
    )
    (net (code "69") (name "unconnected-(IC1-NC-Pad44)") (class "Default")
      (node (ref "IC1") (pin "44") (pinfunction "NC_44") (pintype "bidirectional"))
    )
    (net (code "70") (name "unconnected-(IC1-P0.08-Pad10)") (class "Default")
      (node (ref "IC1") (pin "10") (pinfunction "P0.08_10") (pintype "bidirectional"))
    )
    (net (code "71") (name "unconnected-(IC5-NC-Pad2)") (class "Default")
      (node (ref "IC5") (pin "2") (pinfunction "NC_2") (pintype "bidirectional"))
    )
    (net (code "72") (name "unconnected-(IC5-NC-Pad3)") (class "Default")
      (node (ref "IC5") (pin "3") (pinfunction "NC_3") (pintype "bidirectional"))
    )
    (net (code "73") (name "unconnected-(IC5-NC-Pad4)") (class "Default")
      (node (ref "IC5") (pin "4") (pinfunction "NC_4") (pintype "bidirectional"))
    )
    (net (code "74") (name "unconnected-(IC5-NC-Pad5)") (class "Default")
      (node (ref "IC5") (pin "5") (pinfunction "NC_5") (pintype "bidirectional"))
    )
    (net (code "75") (name "unconnected-(IC5-NC-Pad6)") (class "Default")
      (node (ref "IC5") (pin "6") (pinfunction "NC_6") (pintype "bidirectional"))
    )
    (net (code "76") (name "unconnected-(IC5-NC-Pad14)") (class "Default")
      (node (ref "IC5") (pin "14") (pinfunction "NC_14") (pintype "bidirectional"))
    )
    (net (code "77") (name "unconnected-(IC5-NC-Pad15)") (class "Default")
      (node (ref "IC5") (pin "15") (pinfunction "NC_15") (pintype "bidirectional"))
    )
    (net (code "78") (name "unconnected-(IC5-NC-Pad16)") (class "Default")
      (node (ref "IC5") (pin "16") (pinfunction "NC_16") (pintype "bidirectional"))
    )
    (net (code "79") (name "unconnected-(IC5-NC-Pad17)") (class "Default")
      (node (ref "IC5") (pin "17") (pinfunction "NC_17") (pintype "bidirectional"))
    )
    (net (code "80") (name "unconnected-(IC5-RESV-Pad19)") (class "Default")
      (node (ref "IC5") (pin "19") (pinfunction "RESV_19") (pintype "bidirectional"))
    )
    (net (code "81") (name "unconnected-(U$1-PAD-PadEP)") (class "Default")
      (node (ref "U$1") (pin "EP") (pinfunction "PAD_EP") (pintype "bidirectional"))
    )
    (net (code "82") (name "unconnected-(USBA-S1-PadM1)") (class "Default")
      (node (ref "USB") (pin "M1") (pinfunction "S1_M1") (pintype "passive"))
    )
    (net (code "83") (name "unconnected-(USBA-S2-PadM2)") (class "Default")
      (node (ref "USB") (pin "M2") (pinfunction "S2_M2") (pintype "passive"))
    )
    (net (code "84") (name "unconnected-(USBA-S3-PadM3)") (class "Default")
      (node (ref "USB") (pin "M3") (pinfunction "S3_M3") (pintype "passive"))
    )
    (net (code "85") (name "unconnected-(USBA-S4-PadM4)") (class "Default")
      (node (ref "USB") (pin "M4") (pinfunction "S4_M4") (pintype "passive"))
    )
  )
)
